# Ethernet.net
KiCad netlist of a schematic drawn in Altium Designer
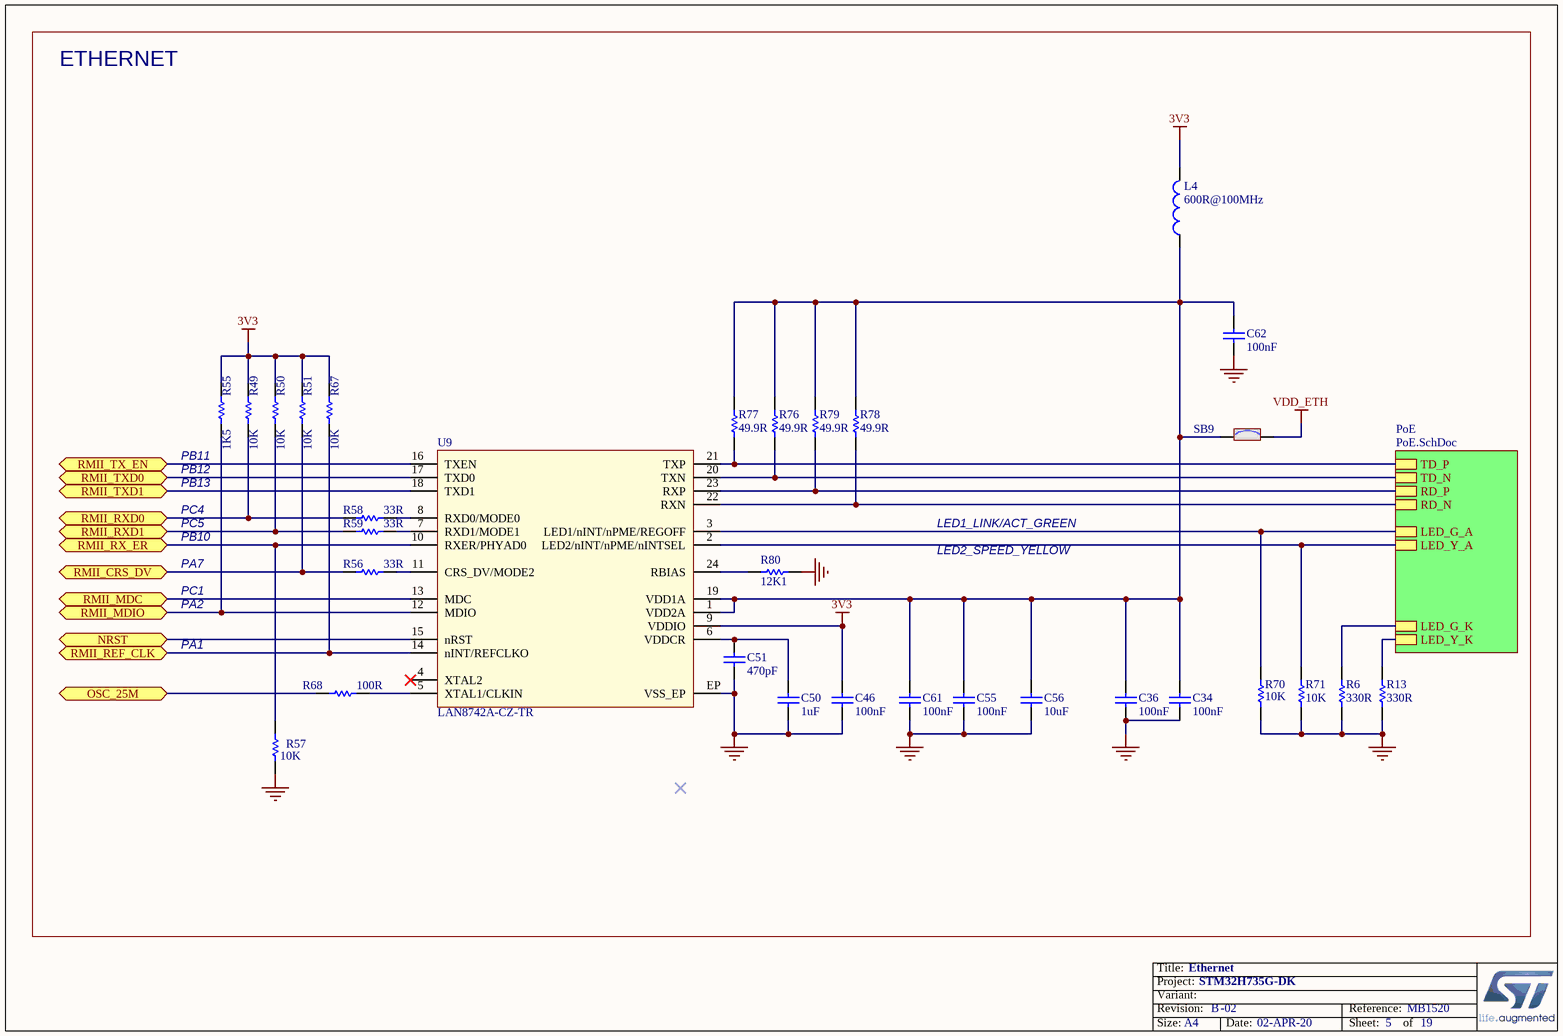
[diagram p0: Ethernet.SchDoc]

(export (version "E")
  (design (tool "Eeschema 10.0.6"))
  (components
    (comp (ref "C34")
      (value "100nF")
      (footprint "C0402")
      (description "Capacitor, MLCC, 100nF, 16V, X7R, 10%, 0402, T=0,5mm")
      (fields
        (field (name "INTERNAL_PART_NUMBER") "MCD-00102")
        (field (name "MANUFACTURER_PART_NUMBER") "CC0402KRX7R7BB104")
        (field (name "PROVIDED_BY") "SUBCO")
      )
      (libsource (lib "MCD_PARTS_database") (part "Capacitor"))
    )
    (comp (ref "C36")
      (value "100nF")
      (footprint "C0402")
      (description "Capacitor, MLCC, 100nF, 16V, X7R, 10%, 0402, T=0,5mm")
      (fields
        (field (name "INTERNAL_PART_NUMBER") "MCD-00102")
        (field (name "MANUFACTURER_PART_NUMBER") "CC0402KRX7R7BB104")
        (field (name "PROVIDED_BY") "SUBCO")
      )
      (libsource (lib "MCD_PARTS_database") (part "Capacitor"))
    )
    (comp (ref "C46")
      (value "100nF")
      (footprint "C0402")
      (description "Capacitor, MLCC, 100nF, 16V, X7R, 10%, 0402, T=0,5mm")
      (fields
        (field (name "INTERNAL_PART_NUMBER") "MCD-00102")
        (field (name "MANUFACTURER_PART_NUMBER") "CC0402KRX7R7BB104")
        (field (name "PROVIDED_BY") "SUBCO")
      )
      (libsource (lib "MCD_PARTS_database") (part "Capacitor"))
    )
    (comp (ref "C50")
      (value "1uF")
      (footprint "C0603")
      (description "Capacitor, MLCC, 1uF, 16V, X5R, 10%, 0603, T=0,8mm")
      (fields
        (field (name "INTERNAL_PART_NUMBER") "MCD-00010")
        (field (name "MANUFACTURER_PART_NUMBER") "CC0603KRX5R7BB105")
        (field (name "PROVIDED_BY") "SUBCO")
      )
      (libsource (lib "MCD_PARTS_database") (part "Capacitor"))
    )
    (comp (ref "C51")
      (value "470pF")
      (footprint "C0402")
      (description "Capacitor, MLCC, 470pF, 50V, NPO, 5%, 0402, T=0,5mm")
      (fields
        (field (name "INTERNAL_PART_NUMBER") "MCD-00724")
        (field (name "MANUFACTURER_PART_NUMBER") "CC0402JRNPO9BN471")
        (field (name "PROVIDED_BY") "SUBCO")
      )
      (libsource (lib "MCD_PARTS_database") (part "Capacitor"))
    )
    (comp (ref "C55")
      (value "100nF")
      (footprint "C0402")
      (description "Capacitor, MLCC, 100nF, 16V, X7R, 10%, 0402, T=0,5mm")
      (fields
        (field (name "INTERNAL_PART_NUMBER") "MCD-00102")
        (field (name "MANUFACTURER_PART_NUMBER") "CC0402KRX7R7BB104")
        (field (name "PROVIDED_BY") "SUBCO")
      )
      (libsource (lib "MCD_PARTS_database") (part "Capacitor"))
    )
    (comp (ref "C56")
      (value "10uF")
      (footprint "C0603")
      (description "Capacitor, MLCC, 10uF, 10V, X5R, 10%, 0603, T=0.8mm")
      (fields
        (field (name "INTERNAL_PART_NUMBER") "MCD-01124")
        (field (name "MANUFACTURER_PART_NUMBER") "GRM188R61A106KAAL")
        (field (name "PROVIDED_BY") "SUBCO")
      )
      (libsource (lib "MCD_PARTS_database") (part "Capacitor"))
    )
    (comp (ref "C61")
      (value "100nF")
      (footprint "C0402")
      (description "Capacitor, MLCC, 100nF, 16V, X7R, 10%, 0402, T=0,5mm")
      (fields
        (field (name "INTERNAL_PART_NUMBER") "MCD-00102")
        (field (name "MANUFACTURER_PART_NUMBER") "CC0402KRX7R7BB104")
        (field (name "PROVIDED_BY") "SUBCO")
      )
      (libsource (lib "MCD_PARTS_database") (part "Capacitor"))
    )
    (comp (ref "C62")
      (value "100nF")
      (footprint "C0402")
      (description "Capacitor, MLCC, 100nF, 16V, X7R, 10%, 0402, T=0,5mm")
      (fields
        (field (name "INTERNAL_PART_NUMBER") "MCD-00102")
        (field (name "MANUFACTURER_PART_NUMBER") "CC0402KRX7R7BB104")
        (field (name "PROVIDED_BY") "SUBCO")
      )
      (libsource (lib "MCD_PARTS_database") (part "Capacitor"))
    )
    (comp (ref "L4")
      (value "600R@100MHz")
      (footprint "L0603")
      (description "SMD Chip ferrite bead, 600R@100MHz +/-25%, 350mA, 500mohm DC, 0603, T=0.8mm")
      (fields
        (field (name "INTERNAL_PART_NUMBER") "MCD-00047")
        (field (name "MANUFACTURER_PART_NUMBER") "FCM1608KF-601T03")
        (field (name "PROVIDED_BY") "SUBCO")
      )
      (libsource (lib "MCD_PARTS_database") (part "BEAD"))
    )
    (comp (ref "R6")
      (value "330R")
      (footprint "R0402")
      (description "Resistor,330R,0402,1%,1/16W")
      (fields
        (field (name "INTERNAL_PART_NUMBER") "MCD-00062")
        (field (name "MANUFACTURER_PART_NUMBER") "RC0402FR-07330RL")
        (field (name "PROVIDED_BY") "SUBCO")
      )
      (libsource (lib "MCD_PARTS_database") (part "Resistor"))
    )
    (comp (ref "R13")
      (value "330R")
      (footprint "R0402")
      (description "Resistor,330R,0402,1%,1/16W")
      (fields
        (field (name "INTERNAL_PART_NUMBER") "MCD-00062")
        (field (name "MANUFACTURER_PART_NUMBER") "RC0402FR-07330RL")
        (field (name "PROVIDED_BY") "SUBCO")
      )
      (libsource (lib "MCD_PARTS_database") (part "Resistor"))
    )
    (comp (ref "R49")
      (value "10K")
      (footprint "R0402")
      (description "Resistor,10K,0402,1%,1/16W")
      (fields
        (field (name "INTERNAL_PART_NUMBER") "MCD-00053")
        (field (name "MANUFACTURER_PART_NUMBER") "RC0402FR-0710KL")
        (field (name "PROVIDED_BY") "SUBCO")
      )
      (libsource (lib "MCD_PARTS_database") (part "Resistor"))
    )
    (comp (ref "R50")
      (value "10K")
      (footprint "R0402")
      (description "Resistor,10K,0402,1%,1/16W")
      (fields
        (field (name "INTERNAL_PART_NUMBER") "MCD-00053")
        (field (name "MANUFACTURER_PART_NUMBER") "RC0402FR-0710KL")
        (field (name "PROVIDED_BY") "SUBCO")
      )
      (libsource (lib "MCD_PARTS_database") (part "Resistor"))
    )
    (comp (ref "R51")
      (value "10K")
      (footprint "R0402")
      (description "Resistor,10K,0402,1%,1/16W")
      (fields
        (field (name "INTERNAL_PART_NUMBER") "MCD-00053")
        (field (name "MANUFACTURER_PART_NUMBER") "RC0402FR-0710KL")
        (field (name "PROVIDED_BY") "SUBCO")
      )
      (libsource (lib "MCD_PARTS_database") (part "Resistor"))
    )
    (comp (ref "R55")
      (value "1K5")
      (footprint "R0402")
      (description "Resistor,1K5,0402,1%,1/16W")
      (fields
        (field (name "INTERNAL_PART_NUMBER") "MCD-00068")
        (field (name "MANUFACTURER_PART_NUMBER") "RC0402FR-071K5L")
        (field (name "PROVIDED_BY") "SUBCO")
      )
      (libsource (lib "MCD_PARTS_database") (part "Resistor"))
    )
    (comp (ref "R56")
      (value "33R")
      (footprint "R0402")
      (description "Resistor,33R,0402,1%,1/16W")
      (fields
        (field (name "INTERNAL_PART_NUMBER") "MCD-00455")
        (field (name "MANUFACTURER_PART_NUMBER") "RC0402FR-0733RL")
        (field (name "PROVIDED_BY") "SUBCO")
      )
      (libsource (lib "MCD_PARTS_database") (part "Resistor"))
    )
    (comp (ref "R57")
      (value "10K")
      (footprint "R0402")
      (description "Resistor,10K,0402,1%,1/16W")
      (fields
        (field (name "INTERNAL_PART_NUMBER") "MCD-00053")
        (field (name "MANUFACTURER_PART_NUMBER") "RC0402FR-0710KL")
        (field (name "PROVIDED_BY") "SUBCO")
      )
      (libsource (lib "MCD_PARTS_database") (part "Resistor"))
    )
    (comp (ref "R58")
      (value "33R")
      (footprint "R0402")
      (description "Resistor,33R,0402,1%,1/16W")
      (fields
        (field (name "INTERNAL_PART_NUMBER") "MCD-00455")
        (field (name "MANUFACTURER_PART_NUMBER") "RC0402FR-0733RL")
        (field (name "PROVIDED_BY") "SUBCO")
      )
      (libsource (lib "MCD_PARTS_database") (part "Resistor"))
    )
    (comp (ref "R59")
      (value "33R")
      (footprint "R0402")
      (description "Resistor,33R,0402,1%,1/16W")
      (fields
        (field (name "INTERNAL_PART_NUMBER") "MCD-00455")
        (field (name "MANUFACTURER_PART_NUMBER") "RC0402FR-0733RL")
        (field (name "PROVIDED_BY") "SUBCO")
      )
      (libsource (lib "MCD_PARTS_database") (part "Resistor"))
    )
    (comp (ref "R67")
      (value "10K")
      (footprint "R0402")
      (description "Resistor,10K,0402,1%,1/16W")
      (fields
        (field (name "INTERNAL_PART_NUMBER") "MCD-00053")
        (field (name "MANUFACTURER_PART_NUMBER") "RC0402FR-0710KL")
        (field (name "PROVIDED_BY") "SUBCO")
      )
      (libsource (lib "MCD_PARTS_database") (part "Resistor"))
    )
    (comp (ref "R68")
      (value "100R")
      (footprint "R0402")
      (description "Resistor,100R,0402,1%,1/16W")
      (fields
        (field (name "INTERNAL_PART_NUMBER") "MCD-00119")
        (field (name "MANUFACTURER_PART_NUMBER") "RC0402FR-07100RL")
        (field (name "PROVIDED_BY") "SUBCO")
      )
      (libsource (lib "MCD_PARTS_database") (part "Resistor"))
    )
    (comp (ref "R70")
      (value "10K")
      (footprint "R0402")
      (description "Resistor,10K,0402,1%,1/16W")
      (fields
        (field (name "INTERNAL_PART_NUMBER") "MCD-00053")
        (field (name "MANUFACTURER_PART_NUMBER") "RC0402FR-0710KL")
        (field (name "PROVIDED_BY") "SUBCO")
      )
      (libsource (lib "MCD_PARTS_database") (part "Resistor"))
    )
    (comp (ref "R71")
      (value "10K")
      (footprint "R0402")
      (description "Resistor,10K,0402,1%,1/16W")
      (fields
        (field (name "INTERNAL_PART_NUMBER") "MCD-00053")
        (field (name "MANUFACTURER_PART_NUMBER") "RC0402FR-0710KL")
        (field (name "PROVIDED_BY") "SUBCO")
      )
      (libsource (lib "MCD_PARTS_database") (part "Resistor"))
    )
    (comp (ref "R76")
      (value "49.9R")
      (footprint "R0402")
      (description "Resistor,49R9,0402,1%,1/16W")
      (fields
        (field (name "INTERNAL_PART_NUMBER") "MCD-00565")
        (field (name "MANUFACTURER_PART_NUMBER") "RC0402FR-0749R9L")
        (field (name "PROVIDED_BY") "SUBCO")
      )
      (libsource (lib "MCD_PARTS_database") (part "Resistor"))
    )
    (comp (ref "R77")
      (value "49.9R")
      (footprint "R0402")
      (description "Resistor,49R9,0402,1%,1/16W")
      (fields
        (field (name "INTERNAL_PART_NUMBER") "MCD-00565")
        (field (name "MANUFACTURER_PART_NUMBER") "RC0402FR-0749R9L")
        (field (name "PROVIDED_BY") "SUBCO")
      )
      (libsource (lib "MCD_PARTS_database") (part "Resistor"))
    )
    (comp (ref "R78")
      (value "49.9R")
      (footprint "R0402")
      (description "Resistor,49R9,0402,1%,1/16W")
      (fields
        (field (name "INTERNAL_PART_NUMBER") "MCD-00565")
        (field (name "MANUFACTURER_PART_NUMBER") "RC0402FR-0749R9L")
        (field (name "PROVIDED_BY") "SUBCO")
      )
      (libsource (lib "MCD_PARTS_database") (part "Resistor"))
    )
    (comp (ref "R79")
      (value "49.9R")
      (footprint "R0402")
      (description "Resistor,49R9,0402,1%,1/16W")
      (fields
        (field (name "INTERNAL_PART_NUMBER") "MCD-00565")
        (field (name "MANUFACTURER_PART_NUMBER") "RC0402FR-0749R9L")
        (field (name "PROVIDED_BY") "SUBCO")
      )
      (libsource (lib "MCD_PARTS_database") (part "Resistor"))
    )
    (comp (ref "R80")
      (value "12K1")
      (footprint "R0402")
      (description "Resistor,12K1,0402,1%,1/16W")
      (fields
        (field (name "INTERNAL_PART_NUMBER") "MCD-00723")
        (field (name "MANUFACTURER_PART_NUMBER") "RC0402FR-0712K1L")
        (field (name "PROVIDED_BY") "SUBCO")
      )
      (libsource (lib "MCD_PARTS_database") (part "Resistor"))
    )
    (comp (ref "SB9")
      (value "SB_ON")
      (footprint "SOLDER-BRIDGE_R0603-0R")
      (description "Solder Bridge ON")
      (fields
        (field (name "INTERNAL_PART_NUMBER") "MCD-00071")
        (field (name "MANUFACTURER_PART_NUMBER") "RC0603JR-070RL")
        (field (name "PROVIDED_BY") "SUBCO")
      )
      (libsource (lib "MCD_PARTS_database") (part "SB_ON"))
    )
    (comp (ref "U9")
      (value "LAN8742A-CZ-TR")
      (footprint "ICC_VQFN24-EPAD_4X4_P050")
      (description "10/100M RMII Ethernet transceiver")
      (fields
        (field (name "INTERNAL_PART_NUMBER") "MCD-00719")
        (field (name "MANUFACTURER") "MICROCHIP")
        (field (name "PROVIDED_BY") "SUBCO")
      )
      (libsource (lib "MCD_PARTS_database") (part "LAN8742A-CZ-TR"))
    )
  )
  (nets
    (net (code "1") (name "/LED_G_A") (class "Default")
      (node (ref "R70") (pin "1") (pinfunction "1_1") (pintype "passive"))
      (node (ref "U9") (pin "3") (pinfunction "LED1/nINT/nPME/REGOFF_3") (pintype "passive"))
    )
    (net (code "2") (name "/LED_G_K") (class "Default")
      (node (ref "R6") (pin "2") (pinfunction "2_2") (pintype "passive"))
    )
    (net (code "3") (name "/LED_Y_A") (class "Default")
      (node (ref "R71") (pin "2") (pinfunction "2_2") (pintype "passive"))
      (node (ref "U9") (pin "2") (pinfunction "LED2/nINT/nPME/nINTSEL_2") (pintype "passive"))
    )
    (net (code "4") (name "/LED_Y_K") (class "Default")
      (node (ref "R13") (pin "2") (pinfunction "2_2") (pintype "passive"))
    )
    (net (code "5") (name "/NRST") (class "Default")
      (node (ref "U9") (pin "15") (pinfunction "nRST_15") (pintype "passive"))
    )
    (net (code "6") (name "/OSC_25M") (class "Default")
      (node (ref "R68") (pin "1") (pinfunction "1_1") (pintype "passive"))
    )
    (net (code "7") (name "/RD_N") (class "Default")
      (node (ref "R78") (pin "1") (pinfunction "1_1") (pintype "passive"))
      (node (ref "U9") (pin "22") (pinfunction "RXN_22") (pintype "passive"))
    )
    (net (code "8") (name "/RD_P") (class "Default")
      (node (ref "R79") (pin "1") (pinfunction "1_1") (pintype "passive"))
      (node (ref "U9") (pin "23") (pinfunction "RXP_23") (pintype "passive"))
    )
    (net (code "9") (name "/RMII_CRS_DV") (class "Default")
      (node (ref "R51") (pin "2") (pinfunction "2_2") (pintype "passive"))
      (node (ref "R56") (pin "1") (pinfunction "1_1") (pintype "passive"))
    )
    (net (code "10") (name "/RMII_MDC") (class "Default")
      (node (ref "U9") (pin "13") (pinfunction "MDC_13") (pintype "passive"))
    )
    (net (code "11") (name "/RMII_MDIO") (class "Default")
      (node (ref "R55") (pin "1") (pinfunction "1_1") (pintype "passive"))
      (node (ref "U9") (pin "12") (pinfunction "MDIO_12") (pintype "passive"))
    )
    (net (code "12") (name "/RMII_REF_CLK") (class "Default")
      (node (ref "R67") (pin "2") (pinfunction "2_2") (pintype "passive"))
      (node (ref "U9") (pin "14") (pinfunction "nINT/REFCLKO_14") (pintype "passive"))
    )
    (net (code "13") (name "/RMII_RXD0") (class "Default")
      (node (ref "R49") (pin "1") (pinfunction "1_1") (pintype "passive"))
      (node (ref "R58") (pin "1") (pinfunction "1_1") (pintype "passive"))
    )
    (net (code "14") (name "/RMII_RXD1") (class "Default")
      (node (ref "R50") (pin "1") (pinfunction "1_1") (pintype "passive"))
      (node (ref "R59") (pin "1") (pinfunction "1_1") (pintype "passive"))
    )
    (net (code "15") (name "/RMII_RX_ER") (class "Default")
      (node (ref "R57") (pin "1") (pinfunction "1_1") (pintype "passive"))
      (node (ref "U9") (pin "10") (pinfunction "RXER/PHYAD0_10") (pintype "passive"))
    )
    (net (code "16") (name "/RMII_TXD0") (class "Default")
      (node (ref "U9") (pin "17") (pinfunction "TXD0_17") (pintype "passive"))
    )
    (net (code "17") (name "/RMII_TXD1") (class "Default")
      (node (ref "U9") (pin "18") (pinfunction "TXD1_18") (pintype "passive"))
    )
    (net (code "18") (name "/RMII_TX_EN") (class "Default")
      (node (ref "U9") (pin "16") (pinfunction "TXEN_16") (pintype "passive"))
    )
    (net (code "19") (name "/TD_N") (class "Default")
      (node (ref "R76") (pin "1") (pinfunction "1_1") (pintype "passive"))
      (node (ref "U9") (pin "20") (pinfunction "TXN_20") (pintype "passive"))
    )
    (net (code "20") (name "/TD_P") (class "Default")
      (node (ref "R77") (pin "1") (pinfunction "1_1") (pintype "passive"))
      (node (ref "U9") (pin "21") (pinfunction "TXP_21") (pintype "passive"))
    )
    (net (code "21") (name "3V3") (class "Default")
      (node (ref "C46") (pin "1") (pinfunction "1_1") (pintype "passive"))
      (node (ref "L4") (pin "2") (pinfunction "2_2") (pintype "passive"))
      (node (ref "R49") (pin "2") (pinfunction "2_2") (pintype "passive"))
      (node (ref "R50") (pin "2") (pinfunction "2_2") (pintype "passive"))
      (node (ref "R51") (pin "1") (pinfunction "1_1") (pintype "passive"))
      (node (ref "R55") (pin "2") (pinfunction "2_2") (pintype "passive"))
      (node (ref "R67") (pin "1") (pinfunction "1_1") (pintype "passive"))
      (node (ref "U9") (pin "9") (pinfunction "VDDIO_9") (pintype "passive"))
    )
    (net (code "22") (name "GND") (class "Default")
      (node (ref "C34") (pin "2") (pinfunction "2_2") (pintype "passive"))
      (node (ref "C36") (pin "2") (pinfunction "2_2") (pintype "passive"))
      (node (ref "C46") (pin "2") (pinfunction "2_2") (pintype "passive"))
      (node (ref "C50") (pin "1") (pinfunction "1_1") (pintype "passive"))
      (node (ref "C51") (pin "1") (pinfunction "1_1") (pintype "passive"))
      (node (ref "C55") (pin "2") (pinfunction "2_2") (pintype "passive"))
      (node (ref "C56") (pin "1") (pinfunction "1_1") (pintype "passive"))
      (node (ref "C61") (pin "2") (pinfunction "2_2") (pintype "passive"))
      (node (ref "C62") (pin "1") (pinfunction "1_1") (pintype "passive"))
      (node (ref "R13") (pin "1") (pinfunction "1_1") (pintype "passive"))
      (node (ref "R57") (pin "2") (pinfunction "2_2") (pintype "passive"))
      (node (ref "R6") (pin "1") (pinfunction "1_1") (pintype "passive"))
      (node (ref "R70") (pin "2") (pinfunction "2_2") (pintype "passive"))
      (node (ref "R71") (pin "1") (pinfunction "1_1") (pintype "passive"))
      (node (ref "R80") (pin "2") (pinfunction "2_2") (pintype "passive"))
      (node (ref "U9") (pin "EP") (pinfunction "VSS_EP_EP") (pintype "passive"))
    )
    (net (code "23") (name "Net-(U9-CRS_DV{slash}MODE2)") (class "Default")
      (node (ref "R56") (pin "2") (pinfunction "2_2") (pintype "passive"))
      (node (ref "U9") (pin "11") (pinfunction "CRS_DV/MODE2_11") (pintype "passive"))
    )
    (net (code "24") (name "Net-(U9-RBIAS)") (class "Default")
      (node (ref "R80") (pin "1") (pinfunction "1_1") (pintype "passive"))
      (node (ref "U9") (pin "24") (pinfunction "RBIAS_24") (pintype "passive"))
    )
    (net (code "25") (name "Net-(U9-RXD0{slash}MODE0)") (class "Default")
      (node (ref "R58") (pin "2") (pinfunction "2_2") (pintype "passive"))
      (node (ref "U9") (pin "8") (pinfunction "RXD0/MODE0_8") (pintype "passive"))
    )
    (net (code "26") (name "Net-(U9-RXD1{slash}MODE1)") (class "Default")
      (node (ref "R59") (pin "2") (pinfunction "2_2") (pintype "passive"))
      (node (ref "U9") (pin "7") (pinfunction "RXD1/MODE1_7") (pintype "passive"))
    )
    (net (code "27") (name "Net-(U9-VDD1A)") (class "Default")
      (node (ref "C34") (pin "1") (pinfunction "1_1") (pintype "passive"))
      (node (ref "C36") (pin "1") (pinfunction "1_1") (pintype "passive"))
      (node (ref "C55") (pin "1") (pinfunction "1_1") (pintype "passive"))
      (node (ref "C56") (pin "2") (pinfunction "2_2") (pintype "passive"))
      (node (ref "C61") (pin "1") (pinfunction "1_1") (pintype "passive"))
      (node (ref "C62") (pin "2") (pinfunction "2_2") (pintype "passive"))
      (node (ref "L4") (pin "1") (pinfunction "1_1") (pintype "passive"))
      (node (ref "R76") (pin "2") (pinfunction "2_2") (pintype "passive"))
      (node (ref "R77") (pin "2") (pinfunction "2_2") (pintype "passive"))
      (node (ref "R78") (pin "2") (pinfunction "2_2") (pintype "passive"))
      (node (ref "R79") (pin "2") (pinfunction "2_2") (pintype "passive"))
      (node (ref "SB9") (pin "1") (pinfunction "1_1") (pintype "passive"))
      (node (ref "U9") (pin "1") (pinfunction "VDD2A_1") (pintype "passive"))
      (node (ref "U9") (pin "19") (pinfunction "VDD1A_19") (pintype "passive"))
    )
    (net (code "28") (name "Net-(U9-VDDCR)") (class "Default")
      (node (ref "C50") (pin "2") (pinfunction "2_2") (pintype "passive"))
      (node (ref "C51") (pin "2") (pinfunction "2_2") (pintype "passive"))
      (node (ref "U9") (pin "6") (pinfunction "VDDCR_6") (pintype "passive"))
    )
    (net (code "29") (name "Net-(U9-XTAL1{slash}CLKIN)") (class "Default")
      (node (ref "R68") (pin "2") (pinfunction "2_2") (pintype "passive"))
      (node (ref "U9") (pin "5") (pinfunction "XTAL1/CLKIN_5") (pintype "passive"))
    )
    (net (code "30") (name "VDD_ETH") (class "Default")
      (node (ref "SB9") (pin "2") (pinfunction "2_2") (pintype "passive"))
    )
    (net (code "31") (name "unconnected-(U9-XTAL2-Pad4)") (class "Default")
      (node (ref "U9") (pin "4") (pinfunction "XTAL2_4") (pintype "passive+no_connect"))
    )
  )
)
